# led_pack12_touch.net
KiCad netlist of a schematic drawn in Altium Designer
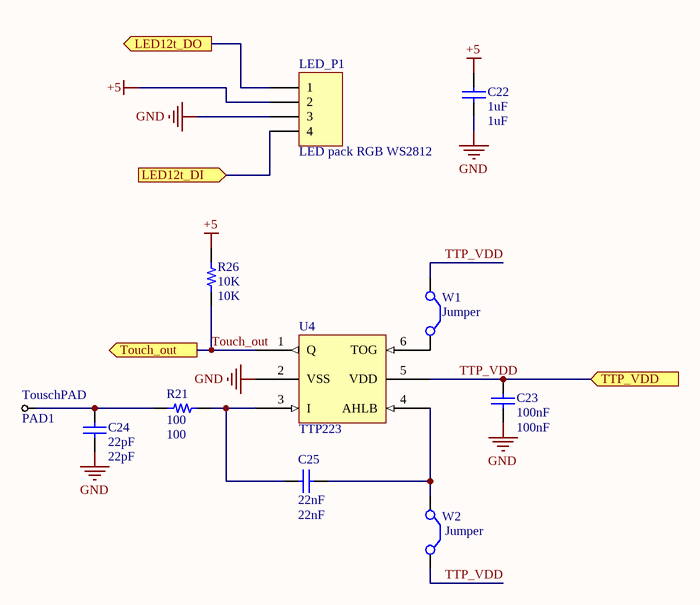
[diagram p0: led_pack12_touch.SchDoc]

(export (version "E")
  (design (tool "Eeschema 10.0.6"))
  (components
    (comp (ref "C22")
      (value "1uF")
      (footprint "0603C")
      (description "CAP SMD 0603")
      (fields (field (name "ALTIUM_VALUE") "1uF") (field (name "PUBLISHER") "Altium Limited"))
      (libsource (lib "Miscellaneous Devices") (part "Cap"))
    )
    (comp (ref "C23")
      (value "100nF")
      (footprint "0603C")
      (description "CAP SMD 0603")
      (fields (field (name "ALTIUM_VALUE") "100nF") (field (name "PUBLISHER") "Altium Limited"))
      (libsource (lib "Miscellaneous Devices") (part "Cap"))
    )
    (comp (ref "C24")
      (value "22pF")
      (footprint "0603C")
      (description "X7R_NPO")
      (fields (field (name "ALTIUM_VALUE") "22pF") (field (name "PUBLISHER") "Altium Limited"))
      (libsource (lib "Miscellaneous Devices") (part "Cap"))
    )
    (comp (ref "C25")
      (value "22nF")
      (footprint "0603C")
      (description "X7R_NPO")
      (fields (field (name "ALTIUM_VALUE") "22nF") (field (name "PUBLISHER") "Altium Limited"))
      (libsource (lib "Miscellaneous Devices") (part "Cap"))
    )
    (comp (ref "LED_P1")
      (value "LED pack RGB WS2812")
      (footprint "PACK124-2121-2")
      (description "8 32mm RGB LED pack")
      (fields (field (name "PUBLISHER") "Altium Limited"))
      (libsource (lib "Altium") (part "Header 4"))
    )
    (comp (ref "PAD1")
      (value "TouschPAD")
      (footprint "touchpad6")
      (libsource (lib "Altium (2)") (part "Test Point"))
    )
    (comp (ref "R21")
      (value "100")
      (footprint "0603R")
      (description "RES SMD 0603")
      (fields (field (name "PART NUMBER") "RCS0805100KFKEA") (field (name "ALTIUM_VALUE") "100"))
      (libsource (lib "lamp control-ver2") (part "Resistor"))
    )
    (comp (ref "R26")
      (value "10K")
      (footprint "0603R")
      (description "RES SMD 0603")
      (fields (field (name "PART NUMBER") "RCS0805100KFKEA") (field (name "ALTIUM_VALUE") "10K"))
      (libsource (lib "lamp control-ver2") (part "Resistor"))
    )
    (comp (ref "U4")
      (value "TTP223")
      (footprint "SOT23-6_L")
      (description "capacitive touch IC")
      (libsource (lib "Schlib1") (part "ttp223b"))
    )
    (comp (ref "W1")
      (value "Jumper")
      (footprint "JUMPER")
      (description "Jumper Wire")
      (fields (field (name "PUBLISHER") "Altium Limited"))
      (libsource (lib "Miscellaneous Devices") (part "Jumper"))
    )
    (comp (ref "W2")
      (value "Jumper")
      (footprint "JUMPER")
      (description "Jumper Wire")
      (fields (field (name "PUBLISHER") "Altium Limited"))
      (libsource (lib "Miscellaneous Devices") (part "Jumper"))
    )
  )
  (nets
    (net (code "1") (name "+5") (class "Default")
      (node (ref "C22") (pin "2") (pinfunction "2_2") (pintype "passive"))
      (node (ref "LED_P1") (pin "2") (pinfunction "2_2") (pintype "passive"))
      (node (ref "R26") (pin "1") (pinfunction "1_1") (pintype "passive"))
    )
    (net (code "2") (name "/LED12t_DI") (class "Default")
      (node (ref "LED_P1") (pin "4") (pinfunction "4_4") (pintype "passive"))
    )
    (net (code "3") (name "/LED12t_DO") (class "Default")
      (node (ref "LED_P1") (pin "1") (pinfunction "1_1") (pintype "passive"))
    )
    (net (code "4") (name "/TTP_VDD") (class "Default")
      (node (ref "C23") (pin "2") (pinfunction "2_2") (pintype "passive"))
      (node (ref "U4") (pin "5") (pinfunction "VDD_5") (pintype "power_in"))
      (node (ref "W1") (pin "1") (pinfunction "C1_1") (pintype "passive"))
      (node (ref "W2") (pin "2") (pinfunction "C2_2") (pintype "passive"))
    )
    (net (code "5") (name "/Touch_out") (class "Default")
      (node (ref "R26") (pin "2") (pinfunction "2_2") (pintype "passive"))
      (node (ref "U4") (pin "1") (pinfunction "Q_1") (pintype "output"))
    )
    (net (code "6") (name "GND") (class "Default")
      (node (ref "C22") (pin "1") (pinfunction "1_1") (pintype "passive"))
      (node (ref "C23") (pin "1") (pinfunction "1_1") (pintype "passive"))
      (node (ref "C24") (pin "1") (pinfunction "1_1") (pintype "passive"))
      (node (ref "LED_P1") (pin "3") (pinfunction "3_3") (pintype "passive"))
      (node (ref "U4") (pin "2") (pinfunction "VSS_2") (pintype "power_in"))
    )
    (net (code "7") (name "Net-(PAD1-T)") (class "Default")
      (node (ref "C24") (pin "2") (pinfunction "2_2") (pintype "passive"))
      (node (ref "PAD1") (pin "1") (pinfunction "T_1") (pintype "passive"))
      (node (ref "R21") (pin "2") (pinfunction "2_2") (pintype "passive"))
    )
    (net (code "8") (name "Net-(U4-AHLB)") (class "Default")
      (node (ref "C25") (pin "1") (pinfunction "1_1") (pintype "passive"))
      (node (ref "U4") (pin "4") (pinfunction "AHLB_4") (pintype "input"))
      (node (ref "W2") (pin "1") (pinfunction "C1_1") (pintype "passive"))
    )
    (net (code "9") (name "Net-(U4-I)") (class "Default")
      (node (ref "C25") (pin "2") (pinfunction "2_2") (pintype "passive"))
      (node (ref "R21") (pin "1") (pinfunction "1_1") (pintype "passive"))
      (node (ref "U4") (pin "3") (pinfunction "I_3") (pintype "input"))
    )
    (net (code "10") (name "Net-(U4-TOG)") (class "Default")
      (node (ref "U4") (pin "6") (pinfunction "TOG_6") (pintype "input"))
      (node (ref "W1") (pin "2") (pinfunction "C2_2") (pintype "passive"))
    )
  )
)
